# Main.net
KiCad netlist of a schematic drawn in Altium Designer
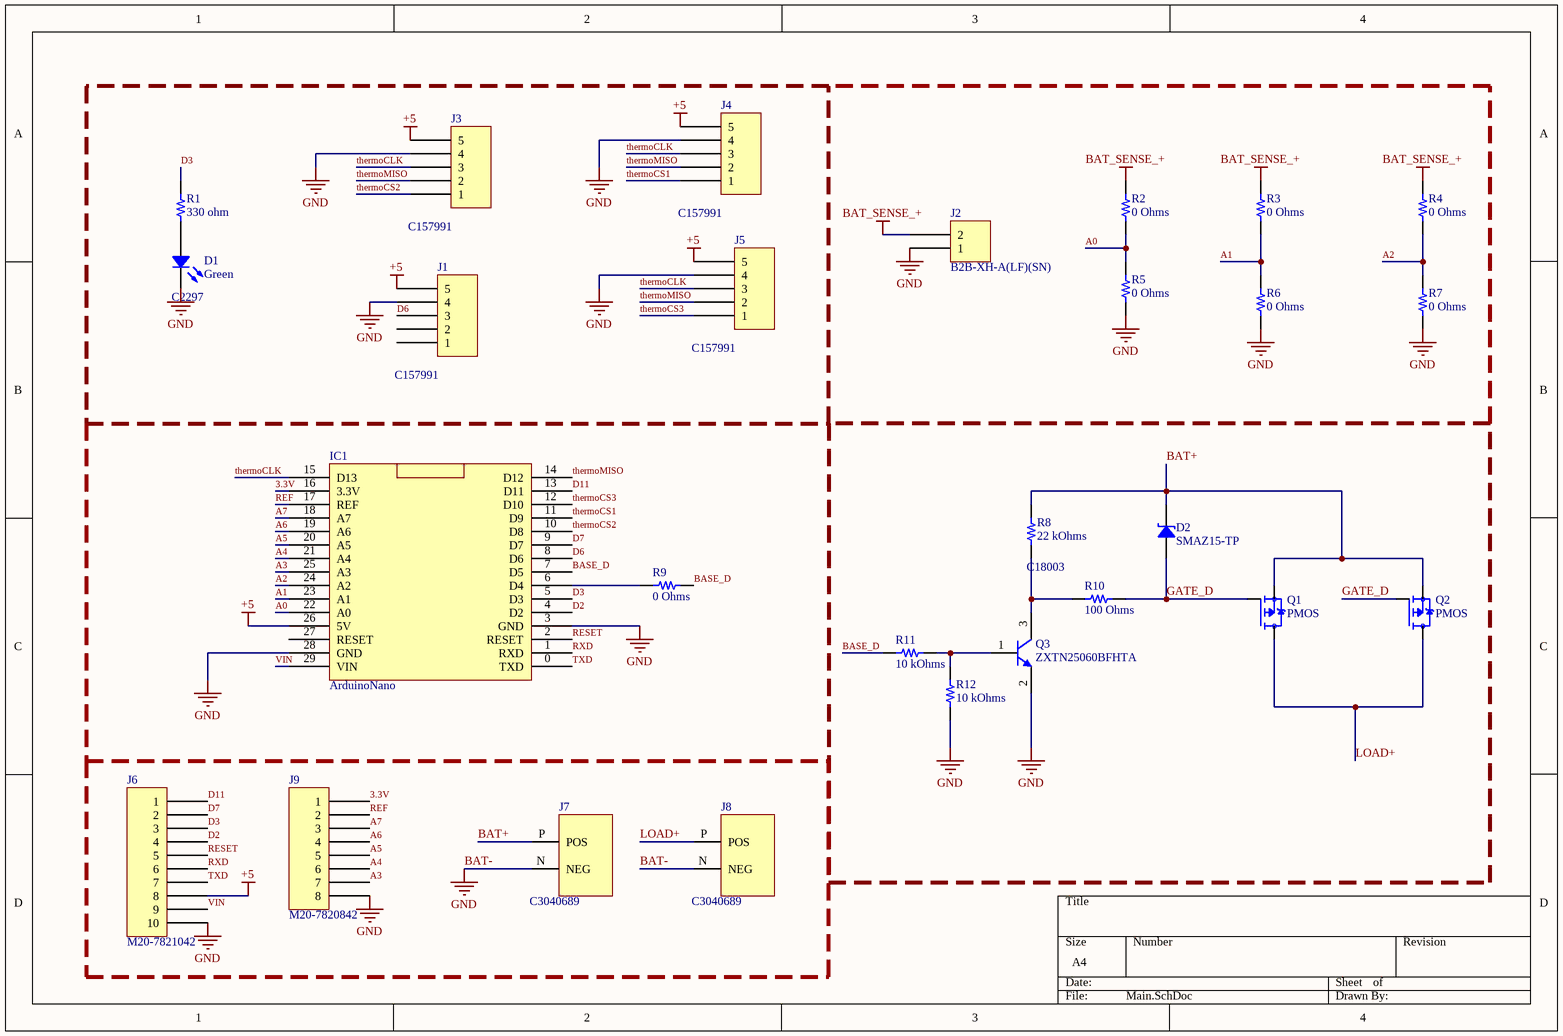
[diagram p0: Main.SchDoc]

(export (version "E")
  (design (tool "Eeschema 10.0.6"))
  (components
    (comp (ref "D1")
      (value "Green")
      (footprint "LED 0805_2012 GREEN")
      (description "LED GREEN DIFFUSED 0805 SMD")
      (fields
        (field (name "PART NUMBER") "597-5311-407NF")
        (field (name "MANUFACTURER") "Dialight")
        (field (name "JLCPCB PART NUMBER") "C2297")
      )
      (libsource (lib "Celestial Altium Library - altium_library (1)") (part "LED"))
    )
    (comp (ref "D2")
      (value "SMAZ15-TP")
      (footprint "DO214AC SMA")
      (description "DIODE ZENER 15V 1W DO214AC")
      (fields (field (name "MANUFACTURER") "Micro Commercial Co") (field (name "TOLERANCE") "±5%"))
      (libsource (lib "Celestial Altium Library - altium_library (1)") (part "Diode Zener"))
    )
    (comp (ref "IC1")
      (value "ArduinoNano")
      (footprint "ArduinoNano_3D")
      (description "ArduinoNano 3D")
      (libsource (lib "altiumlive") (part "ArduinoNano"))
    )
    (comp (ref "J1")
      (value "B5B-XH-A(LF)(SN)")
      (footprint "JST XH B5B-XH-A")
      (description "CONN HEADER VERT 5POS 2.5MM")
      (fields
        (field (name "MANUFACTURER") "JST Sales America Inc.")
        (field (name "JLCPCB PART NUMBER") "C157991")
      )
      (libsource (lib "Celestial Altium Library - altium_library (1)") (part "5 Pin"))
    )
    (comp (ref "J2")
      (value "B2B-XH-A(LF)(SN)")
      (footprint "JST XH B2B-XH-A")
      (description "CONN HEADER VERT 2POS 2.5MM")
      (fields
        (field (name "MANUFACTURER") "JST Sales America Inc.")
        (field (name "JLCPCB PART NUMBER") "C2908600")
      )
      (libsource (lib "Celestial Altium Library - altium_library (1)") (part "2 Pin"))
    )
    (comp (ref "J3")
      (value "B5B-XH-A(LF)(SN)")
      (footprint "JST XH B5B-XH-A")
      (description "CONN HEADER VERT 5POS 2.5MM")
      (fields
        (field (name "MANUFACTURER") "JST Sales America Inc.")
        (field (name "JLCPCB PART NUMBER") "C157991")
      )
      (libsource (lib "Celestial Altium Library - altium_library (1)") (part "5 Pin"))
    )
    (comp (ref "J4")
      (value "B5B-XH-A(LF)(SN)")
      (footprint "JST XH B5B-XH-A")
      (description "CONN HEADER VERT 5POS 2.5MM")
      (fields
        (field (name "MANUFACTURER") "JST Sales America Inc.")
        (field (name "JLCPCB PART NUMBER") "C157991")
      )
      (libsource (lib "Celestial Altium Library - altium_library (1)") (part "5 Pin"))
    )
    (comp (ref "J5")
      (value "B5B-XH-A(LF)(SN)")
      (footprint "JST XH B5B-XH-A")
      (description "CONN HEADER VERT 5POS 2.5MM")
      (fields
        (field (name "MANUFACTURER") "JST Sales America Inc.")
        (field (name "JLCPCB PART NUMBER") "C157991")
      )
      (libsource (lib "Celestial Altium Library - altium_library (1)") (part "5 Pin"))
    )
    (comp (ref "J6")
      (value "M20-7821042")
      (footprint "HARWIN M20-7821045")
      (description "CONN RCPT 10POS 0.1 GOLD PCB")
      (fields (field (name "MANUFACTURER") "Harwin Inc."))
      (libsource (lib "Celestial Altium Library - altium_library (1)") (part "10 Pin"))
    )
    (comp (ref "J7")
      (value "SMT XT90 CONNECTOR")
      (footprint "XT90_PW-M")
      (fields (field (name "JLCPCB PART NUMBER") "C3040689"))
      (libsource (lib "altiumlive") (part "XT90_PW-M"))
    )
    (comp (ref "J8")
      (value "SMT XT90 CONNECTOR")
      (footprint "XT90_PW-M")
      (fields (field (name "JLCPCB PART NUMBER") "C3040689"))
      (libsource (lib "altiumlive") (part "XT90_PW-M"))
    )
    (comp (ref "J9")
      (value "M20-7820842")
      (footprint "HARWIN M20-7820845")
      (description "CONN RCPT 8POS 0.1 GOLD PCB")
      (fields (field (name "MANUFACTURER") "Harwin Inc."))
      (libsource (lib "Celestial Altium Library - altium_library (1)") (part "8 Pin"))
    )
    (comp (ref "Q1")
      (value "PMOS")
      (footprint "TO-263-3-2")
      (fields (field (name "JLCPCB PART NUMBER") "C2909634"))
      (libsource (lib "altiumlive") (part "PMOS"))
    )
    (comp (ref "Q2")
      (value "PMOS")
      (footprint "TO-263-3-2")
      (fields (field (name "JLCPCB PART NUMBER") "C2909634"))
      (libsource (lib "altiumlive") (part "PMOS"))
    )
    (comp (ref "Q3")
      (value "ZXTN25060BFHTA")
      (footprint "DIODES SOT-23-3")
      (description "TRANS NPN 60V 3.5A SOT23-3")
      (fields (field (name "MANUFACTURER") "Diodes Incorporated") (field (name "JLCPCB PART NUMBER") "C2145"))
      (libsource (lib "Celestial Altium Library - altium_library (1)") (part "DIODES INC NPN SOT-23-3"))
    )
    (comp (ref "R1")
      (value "330 ohm")
      (footprint "RES 1206_3216")
      (description "RES SMD 0 OHM JUMPER 1/4W 1206")
      (fields
        (field (name "PART NUMBER") "CRG1206ZR")
        (field (name "MANUFACTURER") "TE Connectivity Passive Product")
      )
      (libsource (lib "Celestial Altium Library - altium_library (1)") (part "Resistor"))
    )
    (comp (ref "R2")
      (value "0 Ohms")
      (footprint "RES 1206_3216")
      (description "RES SMD 0 OHM JUMPER 1/4W 1206")
      (fields
        (field (name "PART NUMBER") "CRG1206ZR")
        (field (name "MANUFACTURER") "TE Connectivity Passive Product")
      )
      (libsource (lib "Celestial Altium Library - altium_library (1)") (part "Resistor"))
    )
    (comp (ref "R3")
      (value "0 Ohms")
      (footprint "RES 1206_3216")
      (description "RES SMD 0 OHM JUMPER 1/4W 1206")
      (fields
        (field (name "PART NUMBER") "CRG1206ZR")
        (field (name "MANUFACTURER") "TE Connectivity Passive Product")
      )
      (libsource (lib "Celestial Altium Library - altium_library (1)") (part "Resistor"))
    )
    (comp (ref "R4")
      (value "0 Ohms")
      (footprint "RES 1206_3216")
      (description "RES SMD 0 OHM JUMPER 1/4W 1206")
      (fields
        (field (name "PART NUMBER") "CRG1206ZR")
        (field (name "MANUFACTURER") "TE Connectivity Passive Product")
      )
      (libsource (lib "Celestial Altium Library - altium_library (1)") (part "Resistor"))
    )
    (comp (ref "R5")
      (value "0 Ohms")
      (footprint "RES 1206_3216")
      (description "RES SMD 0 OHM JUMPER 1/4W 1206")
      (fields
        (field (name "PART NUMBER") "CRG1206ZR")
        (field (name "MANUFACTURER") "TE Connectivity Passive Product")
      )
      (libsource (lib "Celestial Altium Library - altium_library (1)") (part "Resistor"))
    )
    (comp (ref "R6")
      (value "0 Ohms")
      (footprint "RES 1206_3216")
      (description "RES SMD 0 OHM JUMPER 1/4W 1206")
      (fields
        (field (name "PART NUMBER") "CRG1206ZR")
        (field (name "MANUFACTURER") "TE Connectivity Passive Product")
      )
      (libsource (lib "Celestial Altium Library - altium_library (1)") (part "Resistor"))
    )
    (comp (ref "R7")
      (value "0 Ohms")
      (footprint "RES 1206_3216")
      (description "RES SMD 0 OHM JUMPER 1/4W 1206")
      (fields
        (field (name "PART NUMBER") "CRG1206ZR")
        (field (name "MANUFACTURER") "TE Connectivity Passive Product")
      )
      (libsource (lib "Celestial Altium Library - altium_library (1)") (part "Resistor"))
    )
    (comp (ref "R8")
      (value "22 kOhms")
      (footprint "RES 1206_3216")
      (description "RES SMD 22K OHM 0.1% 1/4W 1206")
      (fields
        (field (name "PART NUMBER") "ERA-8ARB223V")
        (field (name "MANUFACTURER") "Panasonic Electronic Components")
        (field (name "JLCPCB PART NUMBER") "C18003")
      )
      (libsource (lib "Celestial Altium Library - altium_library (1)") (part "Resistor"))
    )
    (comp (ref "R9")
      (value "0 Ohms")
      (footprint "YAGEO RES RK73 RS73 SG73 0805_2012")
      (description "RESISTOR")
      (fields
        (field (name "PART NUMBER") "RK73Z2ATTED")
        (field (name "MANUFACTURER") "KOA Speer Electronics, Inc.")
      )
      (libsource (lib "Celestial Altium Library - altium_library (1)") (part "Resistor"))
    )
    (comp (ref "R10")
      (value "100 Ohms")
      (footprint "RES 1206_3216")
      (description "RES 100 OHM 5% 3/4W 1206")
      (fields
        (field (name "PART NUMBER") "SG73P2BTTD101J")
        (field (name "MANUFACTURER") "KOA Speer Electronics, Inc.")
      )
      (libsource (lib "Celestial Altium Library - altium_library (1)") (part "Resistor"))
    )
    (comp (ref "R11")
      (value "10 kOhms")
      (footprint "RES 1206_3216")
      (description "RES 10K OHM 0.1% 1/4W 1206")
      (fields
        (field (name "PART NUMBER") "RN73H2BTTD1002B10")
        (field (name "MANUFACTURER") "KOA Speer Electronics, Inc.")
      )
      (libsource (lib "Celestial Altium Library - altium_library (1)") (part "Resistor"))
    )
    (comp (ref "R12")
      (value "10 kOhms")
      (footprint "RES 1206_3216")
      (description "RES 10K OHM 0.1% 1/4W 1206")
      (fields
        (field (name "PART NUMBER") "RN73H2BTTD1002B10")
        (field (name "MANUFACTURER") "KOA Speer Electronics, Inc.")
      )
      (libsource (lib "Celestial Altium Library - altium_library (1)") (part "Resistor"))
    )
  )
  (nets
    (net (code "1") (name "+5") (class "Default")
      (node (ref "IC1") (pin "26") (pinfunction "5V_26") (pintype "passive"))
      (node (ref "J1") (pin "5") (pinfunction "5_5") (pintype "passive"))
      (node (ref "J3") (pin "5") (pinfunction "5_5") (pintype "passive"))
      (node (ref "J4") (pin "5") (pinfunction "5_5") (pintype "passive"))
      (node (ref "J5") (pin "5") (pinfunction "5_5") (pintype "passive"))
      (node (ref "J6") (pin "8") (pinfunction "8_8") (pintype "passive"))
    )
    (net (code "2") (name "/3.3V") (class "Default")
      (node (ref "IC1") (pin "16") (pinfunction "3.3V_16") (pintype "passive"))
      (node (ref "J9") (pin "1") (pinfunction "1_1") (pintype "passive"))
    )
    (net (code "3") (name "/A0") (class "Default")
      (node (ref "IC1") (pin "22") (pinfunction "A0_22") (pintype "passive"))
      (node (ref "R2") (pin "1") (pinfunction "1_1") (pintype "passive"))
      (node (ref "R5") (pin "2") (pinfunction "2_2") (pintype "passive"))
    )
    (net (code "4") (name "/A1") (class "Default")
      (node (ref "IC1") (pin "23") (pinfunction "A1_23") (pintype "passive"))
      (node (ref "R3") (pin "1") (pinfunction "1_1") (pintype "passive"))
      (node (ref "R6") (pin "2") (pinfunction "2_2") (pintype "passive"))
    )
    (net (code "5") (name "/A2") (class "Default")
      (node (ref "IC1") (pin "24") (pinfunction "A2_24") (pintype "passive"))
      (node (ref "R4") (pin "1") (pinfunction "1_1") (pintype "passive"))
      (node (ref "R7") (pin "2") (pinfunction "2_2") (pintype "passive"))
    )
    (net (code "6") (name "/A3") (class "Default")
      (node (ref "IC1") (pin "25") (pinfunction "A3_25") (pintype "passive"))
      (node (ref "J9") (pin "7") (pinfunction "7_7") (pintype "passive"))
    )
    (net (code "7") (name "/A4") (class "Default")
      (node (ref "IC1") (pin "21") (pinfunction "A4_21") (pintype "passive"))
      (node (ref "J9") (pin "6") (pinfunction "6_6") (pintype "passive"))
    )
    (net (code "8") (name "/A5") (class "Default")
      (node (ref "IC1") (pin "20") (pinfunction "A5_20") (pintype "passive"))
      (node (ref "J9") (pin "5") (pinfunction "5_5") (pintype "passive"))
    )
    (net (code "9") (name "/A6") (class "Default")
      (node (ref "IC1") (pin "19") (pinfunction "A6_19") (pintype "passive"))
      (node (ref "J9") (pin "4") (pinfunction "4_4") (pintype "passive"))
    )
    (net (code "10") (name "/A7") (class "Default")
      (node (ref "IC1") (pin "18") (pinfunction "A7_18") (pintype "passive"))
      (node (ref "J9") (pin "3") (pinfunction "3_3") (pintype "passive"))
    )
    (net (code "11") (name "/BASE_D") (class "Default")
      (node (ref "IC1") (pin "7") (pinfunction "D5_7") (pintype "passive"))
      (node (ref "R11") (pin "1") (pinfunction "1_1") (pintype "passive"))
      (node (ref "R9") (pin "1") (pinfunction "1_1") (pintype "passive"))
    )
    (net (code "12") (name "/BAT+") (class "Default")
      (node (ref "D2") (pin "2") (pinfunction "2_2") (pintype "passive"))
      (node (ref "J7") (pin "P") (pinfunction "POS_P") (pintype "passive"))
      (node (ref "Q1") (pin "2") (pinfunction "S_2") (pintype "passive"))
      (node (ref "Q2") (pin "2") (pinfunction "S_2") (pintype "passive"))
      (node (ref "R8") (pin "2") (pinfunction "2_2") (pintype "passive"))
    )
    (net (code "13") (name "/D2") (class "Default")
      (node (ref "IC1") (pin "4") (pinfunction "D2_4") (pintype "passive"))
      (node (ref "J6") (pin "4") (pinfunction "4_4") (pintype "passive"))
    )
    (net (code "14") (name "/D3") (class "Default")
      (node (ref "IC1") (pin "5") (pinfunction "D3_5") (pintype "passive"))
      (node (ref "J6") (pin "3") (pinfunction "3_3") (pintype "passive"))
      (node (ref "R1") (pin "2") (pinfunction "2_2") (pintype "passive"))
    )
    (net (code "15") (name "/D6") (class "Default")
      (node (ref "IC1") (pin "8") (pinfunction "D6_8") (pintype "passive"))
      (node (ref "J1") (pin "3") (pinfunction "3_3") (pintype "passive"))
    )
    (net (code "16") (name "/D7") (class "Default")
      (node (ref "IC1") (pin "9") (pinfunction "D7_9") (pintype "passive"))
      (node (ref "J6") (pin "2") (pinfunction "2_2") (pintype "passive"))
    )
    (net (code "17") (name "/D11") (class "Default")
      (node (ref "IC1") (pin "13") (pinfunction "D11_13") (pintype "passive"))
      (node (ref "J6") (pin "1") (pinfunction "1_1") (pintype "passive"))
    )
    (net (code "18") (name "/GATE_D") (class "Default")
      (node (ref "D2") (pin "1") (pinfunction "1_1") (pintype "passive"))
      (node (ref "Q1") (pin "1") (pinfunction "G_1") (pintype "passive"))
      (node (ref "Q2") (pin "1") (pinfunction "G_1") (pintype "passive"))
      (node (ref "R10") (pin "2") (pinfunction "2_2") (pintype "passive"))
    )
    (net (code "19") (name "/LOAD+") (class "Default")
      (node (ref "J8") (pin "P") (pinfunction "POS_P") (pintype "passive"))
      (node (ref "Q1") (pin "3") (pinfunction "D_3") (pintype "passive"))
      (node (ref "Q2") (pin "3") (pinfunction "D_3") (pintype "passive"))
    )
    (net (code "20") (name "/REF") (class "Default")
      (node (ref "IC1") (pin "17") (pinfunction "REF_17") (pintype "passive"))
      (node (ref "J9") (pin "2") (pinfunction "2_2") (pintype "passive"))
    )
    (net (code "21") (name "/RESET") (class "Default")
      (node (ref "IC1") (pin "2") (pinfunction "RESET_2") (pintype "passive"))
      (node (ref "J6") (pin "5") (pinfunction "5_5") (pintype "passive"))
    )
    (net (code "22") (name "/RXD") (class "Default")
      (node (ref "IC1") (pin "1") (pinfunction "RXD_1") (pintype "passive"))
      (node (ref "J6") (pin "6") (pinfunction "6_6") (pintype "passive"))
    )
    (net (code "23") (name "/TXD") (class "Default")
      (node (ref "IC1") (pin "0") (pinfunction "TXD_0") (pintype "passive"))
      (node (ref "J6") (pin "7") (pinfunction "7_7") (pintype "passive"))
    )
    (net (code "24") (name "/VIN") (class "Default")
      (node (ref "IC1") (pin "29") (pinfunction "VIN_29") (pintype "passive"))
      (node (ref "J6") (pin "9") (pinfunction "9_9") (pintype "passive"))
    )
    (net (code "25") (name "/thermoCLK") (class "Default")
      (node (ref "IC1") (pin "15") (pinfunction "D13_15") (pintype "passive"))
      (node (ref "J3") (pin "3") (pinfunction "3_3") (pintype "passive"))
      (node (ref "J4") (pin "3") (pinfunction "3_3") (pintype "passive"))
      (node (ref "J5") (pin "3") (pinfunction "3_3") (pintype "passive"))
    )
    (net (code "26") (name "/thermoCS1") (class "Default")
      (node (ref "IC1") (pin "11") (pinfunction "D9_11") (pintype "passive"))
      (node (ref "J4") (pin "1") (pinfunction "1_1") (pintype "passive"))
    )
    (net (code "27") (name "/thermoCS2") (class "Default")
      (node (ref "IC1") (pin "10") (pinfunction "D8_10") (pintype "passive"))
      (node (ref "J3") (pin "1") (pinfunction "1_1") (pintype "passive"))
    )
    (net (code "28") (name "/thermoCS3") (class "Default")
      (node (ref "IC1") (pin "12") (pinfunction "D10_12") (pintype "passive"))
      (node (ref "J5") (pin "1") (pinfunction "1_1") (pintype "passive"))
    )
    (net (code "29") (name "/thermoMISO") (class "Default")
      (node (ref "IC1") (pin "14") (pinfunction "D12_14") (pintype "passive"))
      (node (ref "J3") (pin "2") (pinfunction "2_2") (pintype "passive"))
      (node (ref "J4") (pin "2") (pinfunction "2_2") (pintype "passive"))
      (node (ref "J5") (pin "2") (pinfunction "2_2") (pintype "passive"))
    )
    (net (code "30") (name "BAT_SENSE_+") (class "Default")
      (node (ref "J2") (pin "2") (pinfunction "2_2") (pintype "passive"))
      (node (ref "R2") (pin "2") (pinfunction "2_2") (pintype "passive"))
      (node (ref "R3") (pin "2") (pinfunction "2_2") (pintype "passive"))
      (node (ref "R4") (pin "2") (pinfunction "2_2") (pintype "passive"))
    )
    (net (code "31") (name "GND") (class "Default")
      (node (ref "D1") (pin "2") (pinfunction "2_2") (pintype "passive"))
      (node (ref "IC1") (pin "28") (pinfunction "GND_28") (pintype "passive"))
      (node (ref "IC1") (pin "3") (pinfunction "GND_3") (pintype "passive"))
      (node (ref "J1") (pin "4") (pinfunction "4_4") (pintype "passive"))
      (node (ref "J2") (pin "1") (pinfunction "1_1") (pintype "passive"))
      (node (ref "J3") (pin "4") (pinfunction "4_4") (pintype "passive"))
      (node (ref "J4") (pin "4") (pinfunction "4_4") (pintype "passive"))
      (node (ref "J5") (pin "4") (pinfunction "4_4") (pintype "passive"))
      (node (ref "J6") (pin "10") (pinfunction "10_10") (pintype "passive"))
      (node (ref "J7") (pin "N") (pinfunction "NEG_N") (pintype "passive"))
      (node (ref "J8") (pin "N") (pinfunction "NEG_N") (pintype "passive"))
      (node (ref "J9") (pin "8") (pinfunction "8_8") (pintype "passive"))
      (node (ref "Q3") (pin "2") (pinfunction "E_2") (pintype "passive"))
      (node (ref "R12") (pin "1") (pinfunction "1_1") (pintype "passive"))
      (node (ref "R5") (pin "1") (pinfunction "1_1") (pintype "passive"))
      (node (ref "R6") (pin "1") (pinfunction "1_1") (pintype "passive"))
      (node (ref "R7") (pin "1") (pinfunction "1_1") (pintype "passive"))
    )
    (net (code "32") (name "Net-(D1-Pad1)") (class "Default")
      (node (ref "D1") (pin "1") (pinfunction "1_1") (pintype "passive"))
      (node (ref "R1") (pin "1") (pinfunction "1_1") (pintype "passive"))
    )
    (net (code "33") (name "Net-(IC1-D4)") (class "Default")
      (node (ref "IC1") (pin "6") (pinfunction "D4_6") (pintype "passive"))
      (node (ref "R9") (pin "2") (pinfunction "2_2") (pintype "passive"))
    )
    (net (code "34") (name "Net-(Q3-B)") (class "Default")
      (node (ref "Q3") (pin "1") (pinfunction "B_1") (pintype "passive"))
      (node (ref "R11") (pin "2") (pinfunction "2_2") (pintype "passive"))
      (node (ref "R12") (pin "2") (pinfunction "2_2") (pintype "passive"))
    )
    (net (code "35") (name "Net-(Q3-C)") (class "Default")
      (node (ref "Q3") (pin "3") (pinfunction "C_3") (pintype "passive"))
      (node (ref "R10") (pin "1") (pinfunction "1_1") (pintype "passive"))
      (node (ref "R8") (pin "1") (pinfunction "1_1") (pintype "passive"))
    )
    (net (code "36") (name "unconnected-(IC1-RESET-Pad27)") (class "Default")
      (node (ref "IC1") (pin "27") (pinfunction "RESET_27") (pintype "passive"))
    )
    (net (code "37") (name "unconnected-(J1-Pad1)") (class "Default")
      (node (ref "J1") (pin "1") (pinfunction "1_1") (pintype "passive"))
    )
    (net (code "38") (name "unconnected-(J1-Pad2)") (class "Default")
      (node (ref "J1") (pin "2") (pinfunction "2_2") (pintype "passive"))
    )
  )
)
